# cSLIM-SA_RS485.net
KiCad netlist of a schematic drawn in Altium Designer
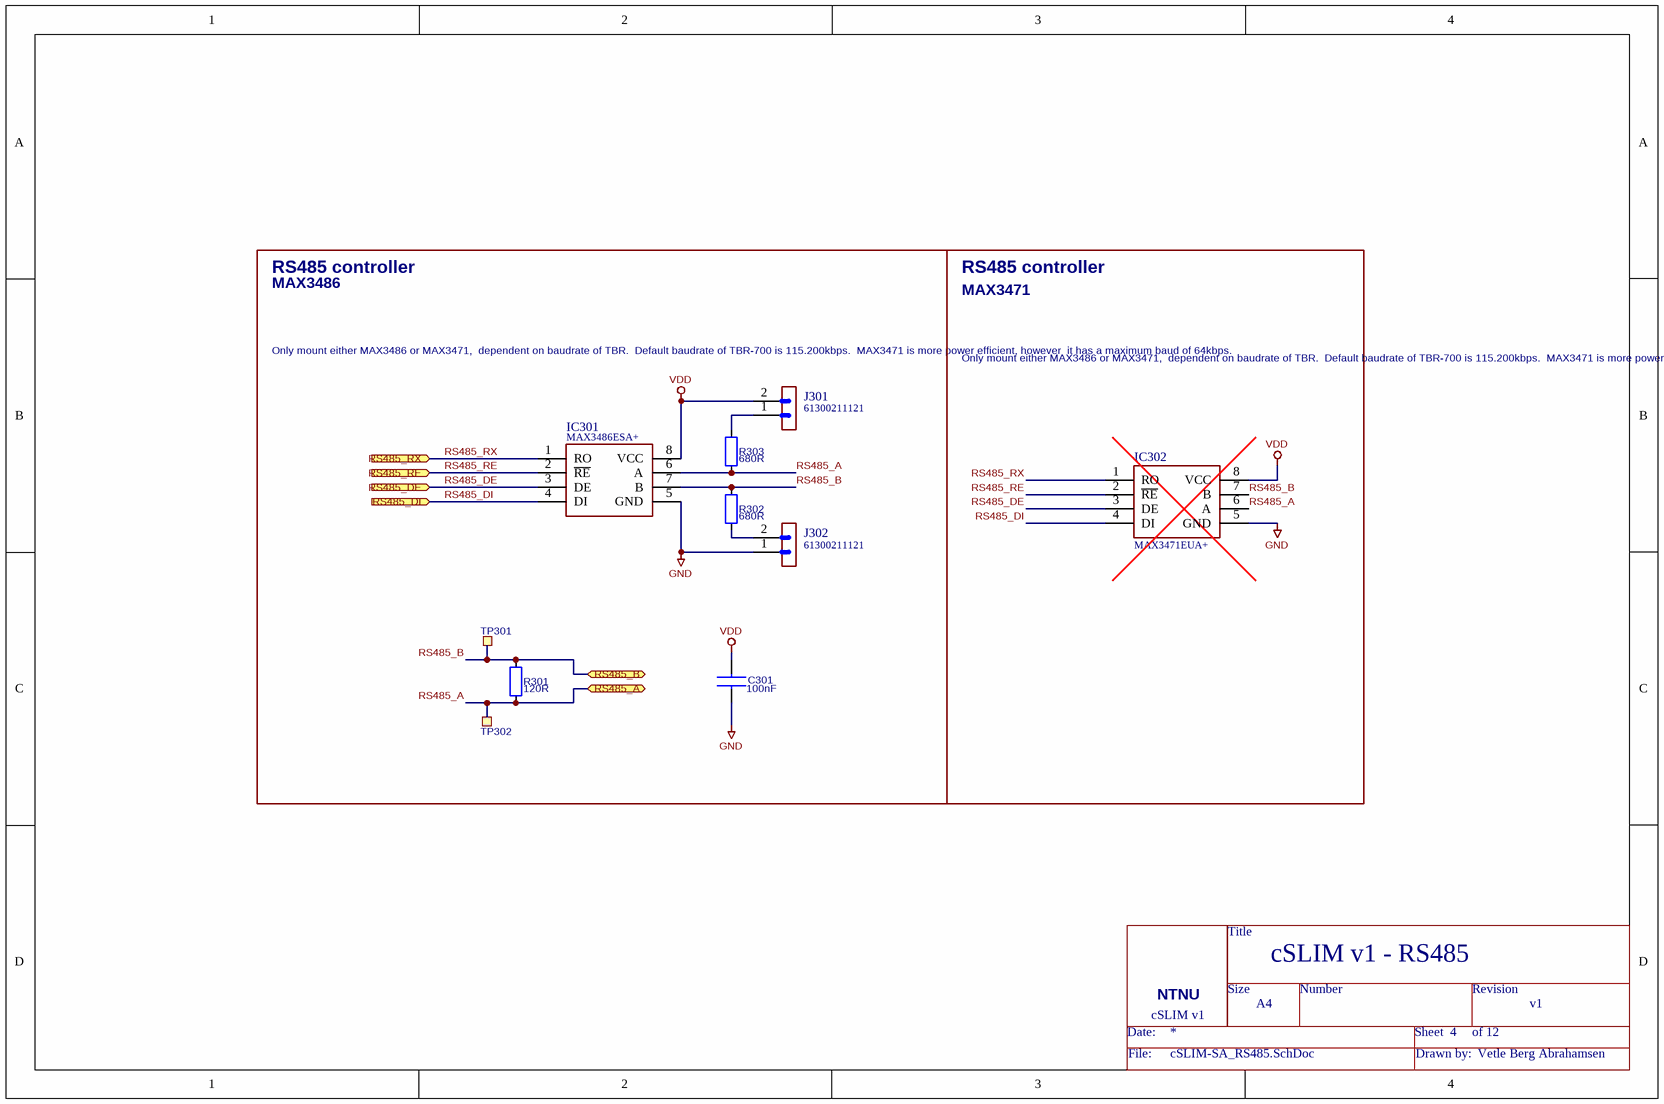
[diagram p0: cSLIM-SA_RS485.SchDoc]

(export (version "E")
  (design (tool "Eeschema 10.0.6"))
  (components
    (comp (ref "C301")
      (value "100nF")
      (footprint "cSLIM-SA:CAPC1608X90N")
      (description "Capacitor")
      (fields (field (name "MANUFACTURER_PART_NUMBER") "CL10B104KB8NNNL"))
      (libsource (lib "cSLIM-SA") (part "C"))
    )
    (comp (ref "IC301")
      (value "MAX3486ESA+")
      (footprint "cSLIM-SA:SOIC127P600X175-8N")
      (description "1/1 Transceiver Half RS422, RS485 8-SOIC")
      (fields (field (name "MOUSER PART NUMBER") "700-MAX3486ESA"))
      (libsource (lib "cSLIM-SA") (part "MAX3486ESA+"))
    )
    (comp (ref "IC302")
      (value "MAX3471EUA+")
      (footprint "cSLIM-SA:SOP65P490X110-8N")
      (description "1/1 Transceiver Half RS422, RS485 8-uMAX-EP¦8-uSOP-EP")
      (fields (field (name "MOUSER PART NUMBER") "700-MAX3471EUA"))
      (libsource (lib "cSLIM-SA") (part "MAX3471EUA+"))
    )
    (comp (ref "J301")
      (value "61300211121")
      (footprint "cSLIM-SA:HDRV2W110P0X254_1X2_508X254X854P")
      (description "CONN HEADER VERT 2POS 2.54MM")
      (fields (field (name "MOUSER PART NUMBER") "710-61300211121"))
      (libsource (lib "cSLIM-SA") (part "61300211121"))
    )
    (comp (ref "J302")
      (value "61300211121")
      (footprint "cSLIM-SA:HDRV2W110P0X254_1X2_508X254X854P")
      (description "CONN HEADER VERT 2POS 2.54MM")
      (fields (field (name "MOUSER PART NUMBER") "710-61300211121"))
      (libsource (lib "cSLIM-SA") (part "61300211121"))
    )
    (comp (ref "R301")
      (value "120R")
      (footprint "cSLIM-SA:RESC1608X55N")
      (fields (field (name "MANUFACTURER_PART_NUMBER") "RT0603DRD07120RL"))
      (libsource (lib "cSLIM-SA") (part "R"))
    )
    (comp (ref "R302")
      (value "680R")
      (footprint "cSLIM-SA:RESC1608X55N")
      (fields (field (name "MANUFACTURER_PART_NUMBER") "RC0603JR-07680RL"))
      (libsource (lib "cSLIM-SA") (part "R"))
    )
    (comp (ref "R303")
      (value "680R")
      (footprint "cSLIM-SA:RESC1608X55N")
      (fields (field (name "MANUFACTURER_PART_NUMBER") "RC0603JR-07680RL"))
      (libsource (lib "cSLIM-SA") (part "R"))
    )
    (comp (ref "TP301")
      (value "TP")
      (footprint "cSLIM-SA:TP_SMD_Ø1.0mm")
      (description "Test points")
      (libsource (lib "") (part "TP_1"))
    )
    (comp (ref "TP302")
      (value "TP")
      (footprint "cSLIM-SA:TP_SMD_Ø1.0mm")
      (description "Test points")
      (libsource (lib "cSLIM-SA") (part "TP"))
    )
  )
  (nets
    (net (code "1") (name "/RS485_A") (class "Default")
      (node (ref "IC301") (pin "6") (pinfunction "A_6") (pintype "passive"))
      (node (ref "IC302") (pin "6") (pinfunction "A_6") (pintype "passive"))
      (node (ref "R301") (pin "2") (pinfunction "2_2") (pintype "passive"))
      (node (ref "R303") (pin "2") (pinfunction "2_2") (pintype "passive"))
      (node (ref "TP302") (pin "1") (pinfunction "1_1") (pintype "passive"))
    )
    (net (code "2") (name "/RS485_B") (class "Default")
      (node (ref "IC301") (pin "7") (pinfunction "B_7") (pintype "passive"))
      (node (ref "IC302") (pin "7") (pinfunction "B_7") (pintype "passive"))
      (node (ref "R301") (pin "1") (pinfunction "1_1") (pintype "passive"))
      (node (ref "R302") (pin "1") (pinfunction "1_1") (pintype "passive"))
      (node (ref "TP301") (pin "1") (pinfunction "1_1") (pintype "passive"))
    )
    (net (code "3") (name "/RS485_DE") (class "Default")
      (node (ref "IC301") (pin "3") (pinfunction "DE_3") (pintype "passive"))
      (node (ref "IC302") (pin "3") (pinfunction "DE_3") (pintype "passive"))
    )
    (net (code "4") (name "/RS485_DI") (class "Default")
      (node (ref "IC301") (pin "4") (pinfunction "DI_4") (pintype "passive"))
      (node (ref "IC302") (pin "4") (pinfunction "DI_4") (pintype "passive"))
    )
    (net (code "5") (name "/RS485_RE") (class "Default")
      (node (ref "IC301") (pin "2") (pinfunction "~{RE}_2") (pintype "passive"))
      (node (ref "IC302") (pin "2") (pinfunction "~{RE}_2") (pintype "passive"))
    )
    (net (code "6") (name "/RS485_RX") (class "Default")
      (node (ref "IC301") (pin "1") (pinfunction "RO_1") (pintype "passive"))
      (node (ref "IC302") (pin "1") (pinfunction "RO_1") (pintype "passive"))
    )
    (net (code "7") (name "GND") (class "Default")
      (node (ref "C301") (pin "2") (pinfunction "2_2") (pintype "passive"))
      (node (ref "IC301") (pin "5") (pinfunction "GND_5") (pintype "passive"))
      (node (ref "IC302") (pin "5") (pinfunction "GND_5") (pintype "passive"))
      (node (ref "J302") (pin "1") (pinfunction "1_1") (pintype "passive"))
    )
    (net (code "8") (name "Net-(J301-Pad1)") (class "Default")
      (node (ref "J301") (pin "1") (pinfunction "1_1") (pintype "passive"))
      (node (ref "R303") (pin "1") (pinfunction "1_1") (pintype "passive"))
    )
    (net (code "9") (name "Net-(J302-Pad2)") (class "Default")
      (node (ref "J302") (pin "2") (pinfunction "2_2") (pintype "passive"))
      (node (ref "R302") (pin "2") (pinfunction "2_2") (pintype "passive"))
    )
    (net (code "10") (name "VDD") (class "Default")
      (node (ref "C301") (pin "1") (pinfunction "1_1") (pintype "passive"))
      (node (ref "IC301") (pin "8") (pinfunction "VCC_8") (pintype "passive"))
      (node (ref "IC302") (pin "8") (pinfunction "VCC_8") (pintype "passive"))
      (node (ref "J301") (pin "2") (pinfunction "2_2") (pintype "passive"))
    )
  )
)
